# Sheet1.net
KiCad netlist of a schematic drawn in Altium Designer
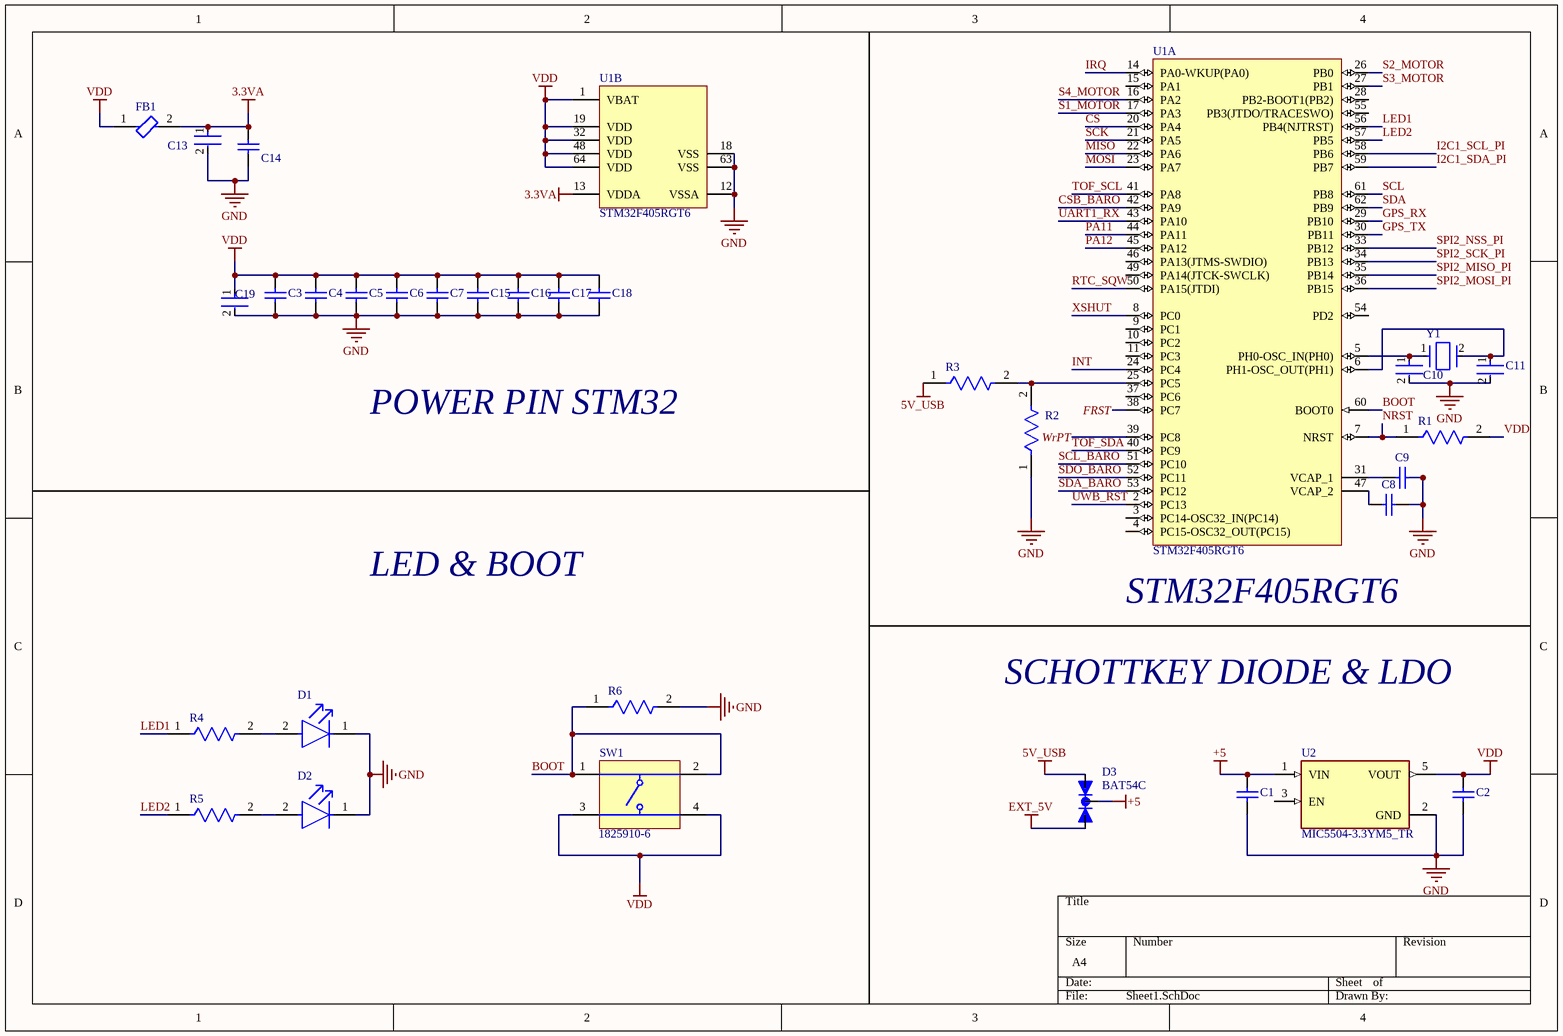
[diagram p0: Sheet1.SchDoc]

(export (version "E")
  (design (tool "Eeschema 10.0.6"))
  (components
    (comp (ref "C1")
      (value "0603YG105ZAT4A")
      (footprint "CAPC1608X90X35ML15T15")
      (fields (field (name "MANUFACTURER") "AVX Interconnect / Elco"))
      (libsource (lib "Altium Content Vault") (part "CAP"))
    )
    (comp (ref "C2")
      (value "0603YG105ZAT4A")
      (footprint "CAPC1608X90X35ML15T15")
      (fields (field (name "MANUFACTURER") "AVX Interconnect / Elco"))
      (libsource (lib "Altium Content Vault") (part "CAP"))
    )
    (comp (ref "C3")
      (value "VJ0603Y104KXXAP")
      (footprint "CAPC1608X92X38NL15T08")
      (fields (field (name "MANUFACTURER") "Vitramon"))
      (libsource (lib "Altium Content Vault") (part "CAP"))
    )
    (comp (ref "C4")
      (value "VJ0603Y104KXXAP")
      (footprint "CAPC1608X92X38NL15T08")
      (fields (field (name "MANUFACTURER") "Vitramon"))
      (libsource (lib "Altium Content Vault") (part "CAP"))
    )
    (comp (ref "C5")
      (value "VJ0603Y104KXXAP")
      (footprint "CAPC1608X92X38NL15T08")
      (fields (field (name "MANUFACTURER") "Vitramon"))
      (libsource (lib "Altium Content Vault") (part "CAP"))
    )
    (comp (ref "C6")
      (value "VJ0603Y104KXXAP")
      (footprint "CAPC1608X92X38NL15T08")
      (fields (field (name "MANUFACTURER") "Vitramon"))
      (libsource (lib "Altium Content Vault") (part "CAP"))
    )
    (comp (ref "C7")
      (value "VJ0603Y104KXXAP")
      (footprint "CAPC1608X92X38NL15T08")
      (fields (field (name "MANUFACTURER") "Vitramon"))
      (libsource (lib "Altium Content Vault") (part "CAP"))
    )
    (comp (ref "C8")
      (value "VJ0603Y104KXXAP")
      (footprint "CAPC1608X92X38NL15T08")
      (description "100nf")
      (fields (field (name "MANUFACTURER") "Vitramon"))
      (libsource (lib "Altium Content Vault") (part "CAP"))
    )
    (comp (ref "C9")
      (value "VJ0603Y104KXXAP")
      (footprint "CAPC1608X92X38NL15T08")
      (description "100nf")
      (fields (field (name "MANUFACTURER") "Vitramon"))
      (libsource (lib "Altium Content Vault") (part "CAP"))
    )
    (comp (ref "C10")
      (value "06035A220JAT2A")
      (footprint "FP-0603-L_1_6_0_15-W_0_81-IPC_C")
      (description "General Purpose Ceramic Capacitor, 0603, 22pF, 5%, NP0, 30ppm/°C, 50V")
      (fields (field (name "VOLTAGE") "50V") (field (name "TOLERANCE") "5%"))
      (libsource (lib "Altium Content Vault") (part "02cd4be3c70576c341d710602a673aa"))
    )
    (comp (ref "C11")
      (value "06035A220JAT2A")
      (footprint "FP-0603-L_1_6_0_15-W_0_81-IPC_C")
      (description "General Purpose Ceramic Capacitor, 0603, 22pF, 5%, NP0, 30ppm/°C, 50V")
      (fields (field (name "VOLTAGE") "50V") (field (name "TOLERANCE") "5%"))
      (libsource (lib "Altium Content Vault") (part "02cd4be3c70576c341d710602a673aa"))
    )
    (comp (ref "C13")
      (value "CGA3E2X7R1H104K080AA")
      (footprint "FP-CGA3E-0_3-0_1-IPC_A")
      (description "Cap Ceramic 100nF 50V X7R 10% Pad SMD 0603 +125°C Automotive T/R")
      (fields (field (name "TOLERANCE") "10%") (field (name "VOLTAGE") "50V"))
      (libsource (lib "Altium Content Vault") (part "b4654b650e69147ec39a6b967a45e02"))
    )
    (comp (ref "C14")
      (value "GRM188R71H103KA01D")
      (footprint "CAPC1608X90X35ML10T15")
      (description "Chip Capacitor, 10 nF, +/- 10%, 50 V, -55 to 125 degC, 0603 (1608 Metric), RoHS, Tape and Reel")
      (fields (field (name "VOLTAGE") "50V") (field (name "TOLERANCE") "10%"))
      (libsource (lib "Altium Content Vault") (part "CAP-NP-2"))
    )
    (comp (ref "C15")
      (value "VJ0603Y104KXXAP")
      (footprint "CAPC1608X92X38NL15T08")
      (fields (field (name "MANUFACTURER") "Vitramon"))
      (libsource (lib "Altium Content Vault") (part "CAP"))
    )
    (comp (ref "C16")
      (value "VJ0603Y104KXXAP")
      (footprint "CAPC1608X92X38NL15T08")
      (fields (field (name "MANUFACTURER") "Vitramon"))
      (libsource (lib "Altium Content Vault") (part "CAP"))
    )
    (comp (ref "C17")
      (value "VJ0603Y104KXXAP")
      (footprint "CAPC1608X92X38NL15T08")
      (fields (field (name "MANUFACTURER") "Vitramon"))
      (libsource (lib "Altium Content Vault") (part "CAP"))
    )
    (comp (ref "C18")
      (value "VJ0603Y104KXXAP")
      (footprint "CAPC1608X92X38NL15T08")
      (fields (field (name "MANUFACTURER") "Vitramon"))
      (libsource (lib "Altium Content Vault") (part "CAP"))
    )
    (comp (ref "C19")
      (value "GRM188R60J106ME47D")
      (footprint "FP-GRM188-0_1-e0_2_0_55-IPC_A")
      (description "Chip Multilayer Ceramic Capacitors for General Purpose, 0603, 10uF, X5R, 15%, 20%, 6.3V")
      (fields (field (name "VOLTAGE") "6.3V") (field (name "TOLERANCE") "20%"))
      (libsource (lib "Altium Content Vault") (part "02cd4be3c70576c341d710602a673aa"))
    )
    (comp (ref "D1")
      (value "LG L29K-G2J1-24-Z")
      (footprint "FP-LG_L29K-MFG")
      (description "LED GREEN DIFFUSED 0603 SMD")
      (libsource (lib "Altium Content Vault") (part "8706943c75ba83719d021d2fdc84c58"))
    )
    (comp (ref "D2")
      (value "VLMS1300-GS08")
      (footprint "FP-6_541-5092_01-4-MFG")
      (description "LED RED 0603 SMD")
      (fields
        (field (name "MANUFACTURER") "Vishay")
        (field (name "OCTOPART") "https://octopart.com/vlms1300-gs08-vishay-21709201")
      )
      (libsource (lib "Altium Content Vault") (part "8706943c75ba83719d021d2fdc84c58"))
    )
    (comp (ref "D3")
      (value "BAT54C")
      (footprint "SOT23-R")
      (fields (field (name "MF") "ON Semiconductor"))
      (libsource (lib "BAT54C") (part "BAT54C"))
    )
    (comp (ref "FB1")
      (value "MPZ2012S101ATD25")
      (footprint "FP-MPZ2012-MFG")
      (description "FERRITE BEAD 100 OHM 0805 1LN")
      (fields (field (name "TOLERANCE") "25%"))
      (libsource (lib "Altium Content Vault") (part "5f30dd21d616792df468990f7003faa"))
    )
    (comp (ref "R1")
      (value "AC0603FR-0710KL")
      (footprint "FP-AC0603-MFG")
      (description "RES 10KΩ 1.00% 0.1W 0603")
      (fields (field (name "TOLERANCE") "1%"))
      (libsource (lib "Altium Content Vault") (part "1029c3af85768c4190bb7ad29bc67b5"))
    )
    (comp (ref "R2")
      (value "MCT06030C1002FP500")
      (footprint "FP-MCT0603-IPC_C")
      (description "RES SMD 100 OHM 1% 1/8W 0603")
      (fields (field (name "TOLERANCE") "1%"))
      (libsource (lib "Altium Content Vault") (part "1029c3af85768c4190bb7ad29bc67b5"))
    )
    (comp (ref "R3")
      (value "MCT06030C1002FP500")
      (footprint "FP-MCT0603-IPC_C")
      (description "RES SMD 100 OHM 1% 1/8W 0603")
      (fields (field (name "TOLERANCE") "1%"))
      (libsource (lib "Altium Content Vault") (part "1029c3af85768c4190bb7ad29bc67b5"))
    )
    (comp (ref "R4")
      (value "AC0603FR-071KL")
      (footprint "FP-AC0603-IPC_B")
      (description "RES 1kΩ 1.00% 0.1W 0603")
      (fields (field (name "TOLERANCE") "1%"))
      (libsource (lib "Altium Content Vault") (part "1029c3af85768c4190bb7ad29bc67b5"))
    )
    (comp (ref "R5")
      (value "AC0603FR-071KL")
      (footprint "FP-AC0603-IPC_B")
      (description "RES 1kΩ 1.00% 0.1W 0603")
      (fields (field (name "TOLERANCE") "1%"))
      (libsource (lib "Altium Content Vault") (part "1029c3af85768c4190bb7ad29bc67b5"))
    )
    (comp (ref "R6")
      (value "AC0603FR-0710KL")
      (footprint "FP-AC0603-MFG")
      (description "RES 10KΩ 1.00% 0.1W 0603")
      (fields (field (name "TOLERANCE") "1%"))
      (libsource (lib "Altium Content Vault") (part "1029c3af85768c4190bb7ad29bc67b5"))
    )
    (comp (ref "SW1")
      (value "1825910-6")
      (footprint "TECO-1825910-6_V")
      (description "Tact Switch, SPST-NO, 0.05 A, -35 to 85 degC, 4-Pin THD, RoHS, Bulk")
      (fields (field (name "MANUFACTURER") "TE Connectivity"))
      (libsource (lib "Altium Content Vault") (part "SW-SPST-4_A"))
    )
    (comp (ref "U1")
      (value "STM32F405RGT6")
      (footprint "STM-LQFP64_M")
      (fields (field (name "MANUFACTURER") "STMicroelectronics"))
      (libsource (lib "Altium Content Vault") (part "MC-ARM-STM32F4X5-SQ64"))
    )
    (comp (ref "U2")
      (value "MIC5504-3.3YM5_TR")
      (footprint "SOT95P280X145-5N")
      (description "Linear Voltage Regulator IC Positive Fixed 1 Output 300mA SOT-23-5")
      (fields (field (name "MF") "Microchip") (field (name "MP") "MIC5504-3.3YM5 TR"))
      (libsource (lib "MIC5504-3.3YM5_TR") (part "MIC5504-3.3YM5_TR"))
    )
    (comp (ref "Y1")
      (value "ABM7-8.000MHZ-8-R80-D2Y-T")
      (footprint "FP-ABM7-MFG")
      (description "Crystal 8MHz ±20ppm 8pF SMD-2 6mm x 3.5mm")
      (libsource (lib "Altium Content Vault") (part "c23a69dc6c9e2f18f2079038eb95dd1"))
    )
  )
  (nets
    (net (code "1") (name "+5") (class "Default")
      (node (ref "C1") (pin "2") (pinfunction "2_2") (pintype "passive"))
      (node (ref "D3") (pin "3") (pinfunction "C_3") (pintype "passive"))
      (node (ref "U2") (pin "1") (pinfunction "VIN_1") (pintype "input"))
    )
    (net (code "2") (name "/BOOT") (class "Default")
      (node (ref "R6") (pin "1") (pinfunction "1_1") (pintype "passive"))
      (node (ref "SW1") (pin "1") (pinfunction "1_1") (pintype "passive"))
      (node (ref "SW1") (pin "2") (pinfunction "2_2") (pintype "passive"))
      (node (ref "U1") (pin "60") (pinfunction "BOOT0_60") (pintype "input"))
    )
    (net (code "3") (name "/CS") (class "Default")
      (node (ref "U1") (pin "20") (pinfunction "PA4_20") (pintype "bidirectional"))
    )
    (net (code "4") (name "/CSB_BARO") (class "Default")
      (node (ref "U1") (pin "42") (pinfunction "PA9_42") (pintype "bidirectional"))
    )
    (net (code "5") (name "/FRST") (class "Default")
      (node (ref "U1") (pin "38") (pinfunction "PC7_38") (pintype "bidirectional"))
    )
    (net (code "6") (name "/GPS_RX") (class "Default")
      (node (ref "U1") (pin "29") (pinfunction "PB10_29") (pintype "bidirectional"))
    )
    (net (code "7") (name "/GPS_TX") (class "Default")
      (node (ref "U1") (pin "30") (pinfunction "PB11_30") (pintype "bidirectional"))
    )
    (net (code "8") (name "/I2C1_SCL_PI") (class "Default")
      (node (ref "U1") (pin "58") (pinfunction "PB6_58") (pintype "bidirectional"))
    )
    (net (code "9") (name "/I2C1_SDA_PI") (class "Default")
      (node (ref "U1") (pin "59") (pinfunction "PB7_59") (pintype "bidirectional"))
    )
    (net (code "10") (name "/INT") (class "Default")
      (node (ref "U1") (pin "24") (pinfunction "PC4_24") (pintype "bidirectional"))
    )
    (net (code "11") (name "/IRQ") (class "Default")
      (node (ref "U1") (pin "14") (pinfunction "PA0-WKUP(PA0)_14") (pintype "bidirectional"))
    )
    (net (code "12") (name "/LED1") (class "Default")
      (node (ref "R4") (pin "1") (pinfunction "1_1") (pintype "passive"))
      (node (ref "U1") (pin "56") (pinfunction "PB4(NJTRST)_56") (pintype "bidirectional"))
    )
    (net (code "13") (name "/LED2") (class "Default")
      (node (ref "R5") (pin "1") (pinfunction "1_1") (pintype "passive"))
      (node (ref "U1") (pin "57") (pinfunction "PB5_57") (pintype "bidirectional"))
    )
    (net (code "14") (name "/MISO") (class "Default")
      (node (ref "U1") (pin "22") (pinfunction "PA6_22") (pintype "bidirectional"))
    )
    (net (code "15") (name "/MOSI") (class "Default")
      (node (ref "U1") (pin "23") (pinfunction "PA7_23") (pintype "bidirectional"))
    )
    (net (code "16") (name "/NRST") (class "Default")
      (node (ref "R1") (pin "1") (pinfunction "1_1") (pintype "passive"))
      (node (ref "U1") (pin "7") (pinfunction "NRST_7") (pintype "bidirectional"))
    )
    (net (code "17") (name "/PA11") (class "Default")
      (node (ref "U1") (pin "44") (pinfunction "PA11_44") (pintype "bidirectional"))
    )
    (net (code "18") (name "/PA12") (class "Default")
      (node (ref "U1") (pin "45") (pinfunction "PA12_45") (pintype "bidirectional"))
    )
    (net (code "19") (name "/RTC_SQW") (class "Default")
      (node (ref "U1") (pin "50") (pinfunction "PA15(JTDI)_50") (pintype "bidirectional"))
    )
    (net (code "20") (name "/S1_MOTOR") (class "Default")
      (node (ref "U1") (pin "17") (pinfunction "PA3_17") (pintype "bidirectional"))
    )
    (net (code "21") (name "/S2_MOTOR") (class "Default")
      (node (ref "U1") (pin "26") (pinfunction "PB0_26") (pintype "bidirectional"))
    )
    (net (code "22") (name "/S3_MOTOR") (class "Default")
      (node (ref "U1") (pin "27") (pinfunction "PB1_27") (pintype "bidirectional"))
    )
    (net (code "23") (name "/S4_MOTOR") (class "Default")
      (node (ref "U1") (pin "16") (pinfunction "PA2_16") (pintype "bidirectional"))
    )
    (net (code "24") (name "/SCK") (class "Default")
      (node (ref "U1") (pin "21") (pinfunction "PA5_21") (pintype "bidirectional"))
    )
    (net (code "25") (name "/SCL") (class "Default")
      (node (ref "U1") (pin "61") (pinfunction "PB8_61") (pintype "bidirectional"))
    )
    (net (code "26") (name "/SCL_BARO") (class "Default")
      (node (ref "U1") (pin "51") (pinfunction "PC10_51") (pintype "bidirectional"))
    )
    (net (code "27") (name "/SDA") (class "Default")
      (node (ref "U1") (pin "62") (pinfunction "PB9_62") (pintype "bidirectional"))
    )
    (net (code "28") (name "/SDA_BARO") (class "Default")
      (node (ref "U1") (pin "53") (pinfunction "PC12_53") (pintype "bidirectional"))
    )
    (net (code "29") (name "/SDO_BARO") (class "Default")
      (node (ref "U1") (pin "52") (pinfunction "PC11_52") (pintype "bidirectional"))
    )
    (net (code "30") (name "/SPI2_MISO_PI") (class "Default")
      (node (ref "U1") (pin "35") (pinfunction "PB14_35") (pintype "bidirectional"))
    )
    (net (code "31") (name "/SPI2_MOSI_PI") (class "Default")
      (node (ref "U1") (pin "36") (pinfunction "PB15_36") (pintype "bidirectional"))
    )
    (net (code "32") (name "/SPI2_NSS_PI") (class "Default")
      (node (ref "U1") (pin "33") (pinfunction "PB12_33") (pintype "bidirectional"))
    )
    (net (code "33") (name "/SPI2_SCK_PI") (class "Default")
      (node (ref "U1") (pin "34") (pinfunction "PB13_34") (pintype "bidirectional"))
    )
    (net (code "34") (name "/TOF_SCL") (class "Default")
      (node (ref "U1") (pin "41") (pinfunction "PA8_41") (pintype "bidirectional"))
    )
    (net (code "35") (name "/TOF_SDA") (class "Default")
      (node (ref "U1") (pin "40") (pinfunction "PC9_40") (pintype "bidirectional"))
    )
    (net (code "36") (name "/UART1_RX") (class "Default")
      (node (ref "U1") (pin "43") (pinfunction "PA10_43") (pintype "bidirectional"))
    )
    (net (code "37") (name "/UWB_RST") (class "Default")
      (node (ref "U1") (pin "2") (pinfunction "PC13_2") (pintype "bidirectional"))
    )
    (net (code "38") (name "/WrPT") (class "Default")
      (node (ref "U1") (pin "39") (pinfunction "PC8_39") (pintype "bidirectional"))
    )
    (net (code "39") (name "/XSHUT") (class "Default")
      (node (ref "U1") (pin "8") (pinfunction "PC0_8") (pintype "bidirectional"))
    )
    (net (code "40") (name "3.3VA") (class "Default")
      (node (ref "C13") (pin "1") (pinfunction "1_1") (pintype "passive"))
      (node (ref "C14") (pin "2") (pinfunction "2_2") (pintype "passive"))
      (node (ref "FB1") (pin "2") (pinfunction "2_2") (pintype "passive"))
      (node (ref "U1") (pin "13") (pinfunction "VDDA_13") (pintype "power_in"))
    )
    (net (code "41") (name "5V_USB") (class "Default")
      (node (ref "D3") (pin "1") (pinfunction "A1_1") (pintype "passive"))
      (node (ref "R3") (pin "1") (pinfunction "1_1") (pintype "passive"))
    )
    (net (code "42") (name "EXT_5V") (class "Default")
      (node (ref "D3") (pin "2") (pinfunction "A2_2") (pintype "passive"))
    )
    (net (code "43") (name "GND") (class "Default")
      (node (ref "C1") (pin "1") (pinfunction "1_1") (pintype "passive"))
      (node (ref "C10") (pin "2") (pinfunction "2_2") (pintype "passive"))
      (node (ref "C11") (pin "2") (pinfunction "2_2") (pintype "passive"))
      (node (ref "C13") (pin "2") (pinfunction "2_2") (pintype "passive"))
      (node (ref "C14") (pin "1") (pinfunction "1_1") (pintype "passive"))
      (node (ref "C15") (pin "1") (pinfunction "1_1") (pintype "passive"))
      (node (ref "C16") (pin "1") (pinfunction "1_1") (pintype "passive"))
      (node (ref "C17") (pin "1") (pinfunction "1_1") (pintype "passive"))
      (node (ref "C18") (pin "1") (pinfunction "1_1") (pintype "passive"))
      (node (ref "C19") (pin "2") (pinfunction "2_2") (pintype "passive"))
      (node (ref "C2") (pin "1") (pinfunction "1_1") (pintype "passive"))
      (node (ref "C3") (pin "1") (pinfunction "1_1") (pintype "passive"))
      (node (ref "C4") (pin "1") (pinfunction "1_1") (pintype "passive"))
      (node (ref "C5") (pin "1") (pinfunction "1_1") (pintype "passive"))
      (node (ref "C6") (pin "1") (pinfunction "1_1") (pintype "passive"))
      (node (ref "C7") (pin "1") (pinfunction "1_1") (pintype "passive"))
      (node (ref "C8") (pin "1") (pinfunction "1_1") (pintype "passive"))
      (node (ref "C9") (pin "1") (pinfunction "1_1") (pintype "passive"))
      (node (ref "D1") (pin "1") (pinfunction "C_1") (pintype "passive"))
      (node (ref "D2") (pin "1") (pinfunction "C_1") (pintype "passive"))
      (node (ref "R2") (pin "1") (pinfunction "1_1") (pintype "passive"))
      (node (ref "R6") (pin "2") (pinfunction "2_2") (pintype "passive"))
      (node (ref "U1") (pin "12") (pinfunction "VSSA_12") (pintype "power_in"))
      (node (ref "U1") (pin "18") (pinfunction "VSS_18") (pintype "power_in"))
      (node (ref "U1") (pin "63") (pinfunction "VSS_63") (pintype "power_in"))
      (node (ref "U2") (pin "2") (pinfunction "GND_2") (pintype "power_in"))
    )
    (net (code "44") (name "Net-(D1-A)") (class "Default")
      (node (ref "D1") (pin "2") (pinfunction "A_2") (pintype "passive"))
      (node (ref "R4") (pin "2") (pinfunction "2_2") (pintype "passive"))
    )
    (net (code "45") (name "Net-(D2-A)") (class "Default")
      (node (ref "D2") (pin "2") (pinfunction "A_2") (pintype "passive"))
      (node (ref "R5") (pin "2") (pinfunction "2_2") (pintype "passive"))
    )
    (net (code "46") (name "Net-(U1A-PC5)") (class "Default")
      (node (ref "R2") (pin "2") (pinfunction "2_2") (pintype "passive"))
      (node (ref "R3") (pin "2") (pinfunction "2_2") (pintype "passive"))
      (node (ref "U1") (pin "25") (pinfunction "PC5_25") (pintype "bidirectional"))
    )
    (net (code "47") (name "Net-(U1A-PH0-OSC_IN(PH0))") (class "Default")
      (node (ref "C10") (pin "1") (pinfunction "1_1") (pintype "passive"))
      (node (ref "U1") (pin "5") (pinfunction "PH0-OSC_IN(PH0)_5") (pintype "bidirectional"))
      (node (ref "Y1") (pin "1") (pinfunction "1_1") (pintype "passive"))
    )
    (net (code "48") (name "Net-(U1A-PH1-OSC_OUT(PH1))") (class "Default")
      (node (ref "C11") (pin "1") (pinfunction "1_1") (pintype "passive"))
      (node (ref "U1") (pin "6") (pinfunction "PH1-OSC_OUT(PH1)_6") (pintype "bidirectional"))
      (node (ref "Y1") (pin "2") (pinfunction "2_2") (pintype "passive"))
    )
    (net (code "49") (name "Net-(U1A-VCAP_1)") (class "Default")
      (node (ref "C9") (pin "2") (pinfunction "2_2") (pintype "passive"))
      (node (ref "U1") (pin "31") (pinfunction "VCAP_1_31") (pintype "power_in"))
    )
    (net (code "50") (name "Net-(U1A-VCAP_2)") (class "Default")
      (node (ref "C8") (pin "2") (pinfunction "2_2") (pintype "passive"))
      (node (ref "U1") (pin "47") (pinfunction "VCAP_2_47") (pintype "power_in"))
    )
    (net (code "51") (name "VDD") (class "Default")
      (node (ref "C15") (pin "2") (pinfunction "2_2") (pintype "passive"))
      (node (ref "C16") (pin "2") (pinfunction "2_2") (pintype "passive"))
      (node (ref "C17") (pin "2") (pinfunction "2_2") (pintype "passive"))
      (node (ref "C18") (pin "2") (pinfunction "2_2") (pintype "passive"))
      (node (ref "C19") (pin "1") (pinfunction "1_1") (pintype "passive"))
      (node (ref "C2") (pin "2") (pinfunction "2_2") (pintype "passive"))
      (node (ref "C3") (pin "2") (pinfunction "2_2") (pintype "passive"))
      (node (ref "C4") (pin "2") (pinfunction "2_2") (pintype "passive"))
      (node (ref "C5") (pin "2") (pinfunction "2_2") (pintype "passive"))
      (node (ref "C6") (pin "2") (pinfunction "2_2") (pintype "passive"))
      (node (ref "C7") (pin "2") (pinfunction "2_2") (pintype "passive"))
      (node (ref "FB1") (pin "1") (pinfunction "1_1") (pintype "passive"))
      (node (ref "R1") (pin "2") (pinfunction "2_2") (pintype "passive"))
      (node (ref "SW1") (pin "3") (pinfunction "3_3") (pintype "passive"))
      (node (ref "SW1") (pin "4") (pinfunction "4_4") (pintype "passive"))
      (node (ref "U1") (pin "1") (pinfunction "VBAT_1") (pintype "power_in"))
      (node (ref "U1") (pin "19") (pinfunction "VDD_19") (pintype "power_in"))
      (node (ref "U1") (pin "32") (pinfunction "VDD_32") (pintype "power_in"))
      (node (ref "U1") (pin "48") (pinfunction "VDD_48") (pintype "power_in"))
      (node (ref "U1") (pin "64") (pinfunction "VDD_64") (pintype "power_in"))
      (node (ref "U2") (pin "5") (pinfunction "VOUT_5") (pintype "output"))
    )
    (net (code "52") (name "unconnected-(U1A-PA1-Pad15)") (class "Default")
      (node (ref "U1") (pin "15") (pinfunction "PA1_15") (pintype "bidirectional"))
    )
    (net (code "53") (name "unconnected-(U1A-PA13(JTMS-SWDIO)-Pad46)") (class "Default")
      (node (ref "U1") (pin "46") (pinfunction "PA13(JTMS-SWDIO)_46") (pintype "bidirectional"))
    )
    (net (code "54") (name "unconnected-(U1A-PA14(JTCK-SWCLK)-Pad49)") (class "Default")
      (node (ref "U1") (pin "49") (pinfunction "PA14(JTCK-SWCLK)_49") (pintype "bidirectional"))
    )
    (net (code "55") (name "unconnected-(U1A-PB2-BOOT1(PB2)-Pad28)") (class "Default")
      (node (ref "U1") (pin "28") (pinfunction "PB2-BOOT1(PB2)_28") (pintype "bidirectional"))
    )
    (net (code "56") (name "unconnected-(U1A-PB3(JTDO{slash}TRACESWO)-Pad55)") (class "Default")
      (node (ref "U1") (pin "55") (pinfunction "PB3(JTDO/TRACESWO)_55") (pintype "bidirectional"))
    )
    (net (code "57") (name "unconnected-(U1A-PC1-Pad9)") (class "Default")
      (node (ref "U1") (pin "9") (pinfunction "PC1_9") (pintype "bidirectional"))
    )
    (net (code "58") (name "unconnected-(U1A-PC2-Pad10)") (class "Default")
      (node (ref "U1") (pin "10") (pinfunction "PC2_10") (pintype "bidirectional"))
    )
    (net (code "59") (name "unconnected-(U1A-PC3-Pad11)") (class "Default")
      (node (ref "U1") (pin "11") (pinfunction "PC3_11") (pintype "bidirectional"))
    )
    (net (code "60") (name "unconnected-(U1A-PC6-Pad37)") (class "Default")
      (node (ref "U1") (pin "37") (pinfunction "PC6_37") (pintype "bidirectional"))
    )
    (net (code "61") (name "unconnected-(U1A-PC14-OSC32_IN(PC14)-Pad3)") (class "Default")
      (node (ref "U1") (pin "3") (pinfunction "PC14-OSC32_IN(PC14)_3") (pintype "bidirectional"))
    )
    (net (code "62") (name "unconnected-(U1A-PC15-OSC32_OUT(PC15)-Pad4)") (class "Default")
      (node (ref "U1") (pin "4") (pinfunction "PC15-OSC32_OUT(PC15)_4") (pintype "bidirectional"))
    )
    (net (code "63") (name "unconnected-(U1A-PD2-Pad54)") (class "Default")
      (node (ref "U1") (pin "54") (pinfunction "PD2_54") (pintype "bidirectional"))
    )
    (net (code "64") (name "unconnected-(U2-EN-Pad3)") (class "Default")
      (node (ref "U2") (pin "3") (pinfunction "EN_3") (pintype "input"))
    )
  )
)
